# Alec_BatteryPack.net
KiCad netlist of a schematic drawn in EAGLE
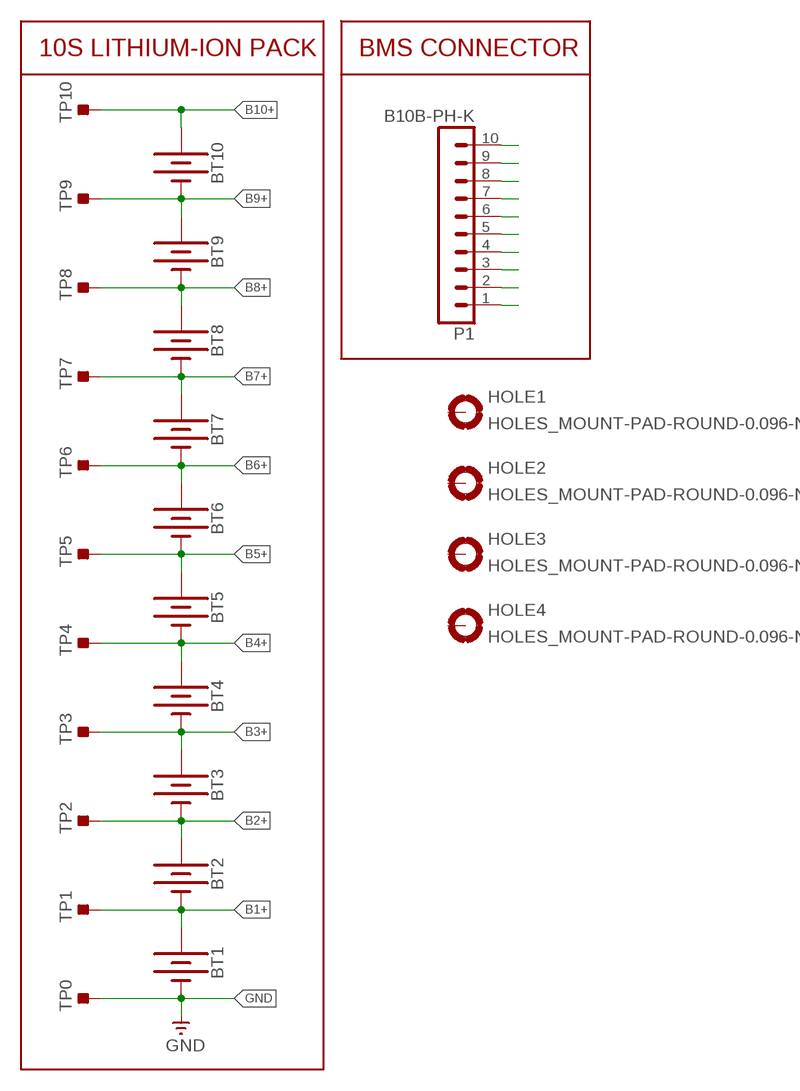
[diagram p0: schematic, sheet 1]

(export (version "E")
  (design (tool "Eeschema 10.0.6"))
  (components
    (comp (ref "BT1")
      (value "BATTERY-18650")
      (footprint "eagle-import:BATTERY_18650-HOLDER")
      (libsource (lib "eagle-import") (part "BATTERY-18650"))
    )
    (comp (ref "BT2")
      (value "BATTERY-18650")
      (footprint "eagle-import:BATTERY_18650-HOLDER")
      (libsource (lib "eagle-import") (part "BATTERY-18650"))
    )
    (comp (ref "BT3")
      (value "BATTERY-18650")
      (footprint "eagle-import:BATTERY_18650-HOLDER")
      (libsource (lib "eagle-import") (part "BATTERY-18650"))
    )
    (comp (ref "BT4")
      (value "BATTERY-18650")
      (footprint "eagle-import:BATTERY_18650-HOLDER")
      (libsource (lib "eagle-import") (part "BATTERY-18650"))
    )
    (comp (ref "BT5")
      (value "BATTERY-18650")
      (footprint "eagle-import:BATTERY_18650-HOLDER")
      (libsource (lib "eagle-import") (part "BATTERY-18650"))
    )
    (comp (ref "BT6")
      (value "BATTERY-18650")
      (footprint "eagle-import:BATTERY_18650-HOLDER")
      (libsource (lib "eagle-import") (part "BATTERY-18650"))
    )
    (comp (ref "BT7")
      (value "BATTERY-18650")
      (footprint "eagle-import:BATTERY_18650-HOLDER")
      (libsource (lib "eagle-import") (part "BATTERY-18650"))
    )
    (comp (ref "BT8")
      (value "BATTERY-18650")
      (footprint "eagle-import:BATTERY_18650-HOLDER")
      (libsource (lib "eagle-import") (part "BATTERY-18650"))
    )
    (comp (ref "BT9")
      (value "BATTERY-18650")
      (footprint "eagle-import:BATTERY_18650-HOLDER")
      (libsource (lib "eagle-import") (part "BATTERY-18650"))
    )
    (comp (ref "BT10")
      (value "BATTERY-18650")
      (footprint "eagle-import:BATTERY_18650-HOLDER")
      (libsource (lib "eagle-import") (part "BATTERY-18650"))
    )
    (comp (ref "HOLE1")
      (value "HOLES_MOUNT-PAD-ROUND-0.096-NS")
      (footprint "eagle-import:HOLES_096-PAD-NS")
      (libsource (lib "eagle-import") (part "HOLES_MOUNT-PAD-ROUND-0.096-NS"))
    )
    (comp (ref "HOLE2")
      (value "HOLES_MOUNT-PAD-ROUND-0.096-NS")
      (footprint "eagle-import:HOLES_096-PAD-NS")
      (libsource (lib "eagle-import") (part "HOLES_MOUNT-PAD-ROUND-0.096-NS"))
    )
    (comp (ref "HOLE3")
      (value "HOLES_MOUNT-PAD-ROUND-0.096-NS")
      (footprint "eagle-import:HOLES_096-PAD-NS")
      (libsource (lib "eagle-import") (part "HOLES_MOUNT-PAD-ROUND-0.096-NS"))
    )
    (comp (ref "HOLE4")
      (value "HOLES_MOUNT-PAD-ROUND-0.096-NS")
      (footprint "eagle-import:HOLES_096-PAD-NS")
      (libsource (lib "eagle-import") (part "HOLES_MOUNT-PAD-ROUND-0.096-NS"))
    )
    (comp (ref "P1")
      (value "B10B-PH-K")
      (footprint "eagle-import:B10B-PH-K")
      (libsource (lib "eagle-import") (part "B10B-PH-K"))
    )
    (comp (ref "TP0")
      (value "TESTPOINT_TPS-SMD-10SN")
      (footprint "eagle-import:TESTPOINT_SMD-10SN")
      (libsource (lib "eagle-import") (part "TESTPOINT_TPS-SMD-10SN"))
    )
    (comp (ref "TP1")
      (value "TESTPOINT_TPS-SMD-10SN")
      (footprint "eagle-import:TESTPOINT_SMD-10SN")
      (libsource (lib "eagle-import") (part "TESTPOINT_TPS-SMD-10SN"))
    )
    (comp (ref "TP2")
      (value "TESTPOINT_TPS-SMD-10SN")
      (footprint "eagle-import:TESTPOINT_SMD-10SN")
      (libsource (lib "eagle-import") (part "TESTPOINT_TPS-SMD-10SN"))
    )
    (comp (ref "TP3")
      (value "TESTPOINT_TPS-SMD-10SN")
      (footprint "eagle-import:TESTPOINT_SMD-10SN")
      (libsource (lib "eagle-import") (part "TESTPOINT_TPS-SMD-10SN"))
    )
    (comp (ref "TP4")
      (value "TESTPOINT_TPS-SMD-10SN")
      (footprint "eagle-import:TESTPOINT_SMD-10SN")
      (libsource (lib "eagle-import") (part "TESTPOINT_TPS-SMD-10SN"))
    )
    (comp (ref "TP5")
      (value "TESTPOINT_TPS-SMD-10SN")
      (footprint "eagle-import:TESTPOINT_SMD-10SN")
      (libsource (lib "eagle-import") (part "TESTPOINT_TPS-SMD-10SN"))
    )
    (comp (ref "TP6")
      (value "TESTPOINT_TPS-SMD-10SN")
      (footprint "eagle-import:TESTPOINT_SMD-10SN")
      (libsource (lib "eagle-import") (part "TESTPOINT_TPS-SMD-10SN"))
    )
    (comp (ref "TP7")
      (value "TESTPOINT_TPS-SMD-10SN")
      (footprint "eagle-import:TESTPOINT_SMD-10SN")
      (libsource (lib "eagle-import") (part "TESTPOINT_TPS-SMD-10SN"))
    )
    (comp (ref "TP8")
      (value "TESTPOINT_TPS-SMD-10SN")
      (footprint "eagle-import:TESTPOINT_SMD-10SN")
      (libsource (lib "eagle-import") (part "TESTPOINT_TPS-SMD-10SN"))
    )
    (comp (ref "TP9")
      (value "TESTPOINT_TPS-SMD-10SN")
      (footprint "eagle-import:TESTPOINT_SMD-10SN")
      (libsource (lib "eagle-import") (part "TESTPOINT_TPS-SMD-10SN"))
    )
    (comp (ref "TP10")
      (value "TESTPOINT_TPS-SMD-10SN")
      (footprint "eagle-import:TESTPOINT_SMD-10SN")
      (libsource (lib "eagle-import") (part "TESTPOINT_TPS-SMD-10SN"))
    )
  )
  (nets
    (net (code "1") (name "B1+") (class "Default")
      (node (ref "BT1") (pin "PWR@1") (pinfunction "+_PWR@1") (pintype "power_in"))
      (node (ref "BT2") (pin "GND@1") (pinfunction "-_GND@1") (pintype "power_in"))
      (node (ref "TP1") (pin "TP") (pinfunction "TP_TP") (pintype "passive"))
    )
    (net (code "2") (name "B2+") (class "Default")
      (node (ref "BT2") (pin "PWR@1") (pinfunction "+_PWR@1") (pintype "power_in"))
      (node (ref "BT3") (pin "GND@1") (pinfunction "-_GND@1") (pintype "power_in"))
      (node (ref "TP2") (pin "TP") (pinfunction "TP_TP") (pintype "passive"))
    )
    (net (code "3") (name "B3+") (class "Default")
      (node (ref "BT3") (pin "PWR@1") (pinfunction "+_PWR@1") (pintype "power_in"))
      (node (ref "BT4") (pin "GND@1") (pinfunction "-_GND@1") (pintype "power_in"))
      (node (ref "TP3") (pin "TP") (pinfunction "TP_TP") (pintype "passive"))
    )
    (net (code "4") (name "B4+") (class "Default")
      (node (ref "BT4") (pin "PWR@1") (pinfunction "+_PWR@1") (pintype "power_in"))
      (node (ref "BT5") (pin "GND@1") (pinfunction "-_GND@1") (pintype "power_in"))
      (node (ref "TP4") (pin "TP") (pinfunction "TP_TP") (pintype "passive"))
    )
    (net (code "5") (name "B5+") (class "Default")
      (node (ref "BT5") (pin "PWR@1") (pinfunction "+_PWR@1") (pintype "power_in"))
      (node (ref "BT6") (pin "GND@1") (pinfunction "-_GND@1") (pintype "power_in"))
      (node (ref "TP5") (pin "TP") (pinfunction "TP_TP") (pintype "passive"))
    )
    (net (code "6") (name "B6+") (class "Default")
      (node (ref "BT6") (pin "PWR@1") (pinfunction "+_PWR@1") (pintype "power_in"))
      (node (ref "BT7") (pin "GND@1") (pinfunction "-_GND@1") (pintype "power_in"))
      (node (ref "TP6") (pin "TP") (pinfunction "TP_TP") (pintype "passive"))
    )
    (net (code "7") (name "B7+") (class "Default")
      (node (ref "BT7") (pin "PWR@1") (pinfunction "+_PWR@1") (pintype "power_in"))
      (node (ref "BT8") (pin "GND@1") (pinfunction "-_GND@1") (pintype "power_in"))
      (node (ref "TP7") (pin "TP") (pinfunction "TP_TP") (pintype "passive"))
    )
    (net (code "8") (name "B8+") (class "Default")
      (node (ref "BT8") (pin "PWR@1") (pinfunction "+_PWR@1") (pintype "power_in"))
      (node (ref "BT9") (pin "GND@1") (pinfunction "-_GND@1") (pintype "power_in"))
      (node (ref "TP8") (pin "TP") (pinfunction "TP_TP") (pintype "passive"))
    )
    (net (code "9") (name "B9+") (class "Default")
      (node (ref "BT10") (pin "GND@1") (pinfunction "-_GND@1") (pintype "power_in"))
      (node (ref "BT9") (pin "PWR@1") (pinfunction "+_PWR@1") (pintype "power_in"))
      (node (ref "TP9") (pin "TP") (pinfunction "TP_TP") (pintype "passive"))
    )
    (net (code "10") (name "B10+") (class "Default")
      (node (ref "BT10") (pin "PWR@1") (pinfunction "+_PWR@1") (pintype "power_in"))
      (node (ref "TP10") (pin "TP") (pinfunction "TP_TP") (pintype "passive"))
    )
    (net (code "11") (name "GND") (class "Default")
      (node (ref "BT1") (pin "GND@1") (pinfunction "-_GND@1") (pintype "power_in"))
      (node (ref "TP0") (pin "TP") (pinfunction "TP_TP") (pintype "passive"))
    )
    (net (code "12") (name "unconnected-(HOLE1-MOUNT-PadB096)") (class "Default")
      (node (ref "HOLE1") (pin "B096") (pinfunction "MOUNT_B096") (pintype "passive"))
    )
    (net (code "13") (name "unconnected-(HOLE2-MOUNT-PadB096)") (class "Default")
      (node (ref "HOLE2") (pin "B096") (pinfunction "MOUNT_B096") (pintype "passive"))
    )
    (net (code "14") (name "unconnected-(HOLE3-MOUNT-PadB096)") (class "Default")
      (node (ref "HOLE3") (pin "B096") (pinfunction "MOUNT_B096") (pintype "passive"))
    )
    (net (code "15") (name "unconnected-(HOLE4-MOUNT-PadB096)") (class "Default")
      (node (ref "HOLE4") (pin "B096") (pinfunction "MOUNT_B096") (pintype "passive"))
    )
    (net (code "16") (name "unconnected-(P1-Pad1)") (class "Default")
      (node (ref "P1") (pin "1") (pinfunction "1_1") (pintype "passive"))
    )
    (net (code "17") (name "unconnected-(P1-Pad2)") (class "Default")
      (node (ref "P1") (pin "2") (pinfunction "2_2") (pintype "passive"))
    )
    (net (code "18") (name "unconnected-(P1-Pad3)") (class "Default")
      (node (ref "P1") (pin "3") (pinfunction "3_3") (pintype "passive"))
    )
    (net (code "19") (name "unconnected-(P1-Pad4)") (class "Default")
      (node (ref "P1") (pin "4") (pinfunction "4_4") (pintype "passive"))
    )
    (net (code "20") (name "unconnected-(P1-Pad5)") (class "Default")
      (node (ref "P1") (pin "5") (pinfunction "5_5") (pintype "passive"))
    )
    (net (code "21") (name "unconnected-(P1-Pad6)") (class "Default")
      (node (ref "P1") (pin "6") (pinfunction "6_6") (pintype "passive"))
    )
    (net (code "22") (name "unconnected-(P1-Pad7)") (class "Default")
      (node (ref "P1") (pin "7") (pinfunction "7_7") (pintype "passive"))
    )
    (net (code "23") (name "unconnected-(P1-Pad8)") (class "Default")
      (node (ref "P1") (pin "8") (pinfunction "8_8") (pintype "passive"))
    )
    (net (code "24") (name "unconnected-(P1-Pad9)") (class "Default")
      (node (ref "P1") (pin "9") (pinfunction "9_9") (pintype "passive"))
    )
    (net (code "25") (name "unconnected-(P1-Pad10)") (class "Default")
      (node (ref "P1") (pin "10") (pinfunction "10_10") (pintype "passive"))
    )
  )
)
